# Kajtu_-DSP_analog_in.net
KiCad netlist of a schematic drawn in Altium Designer
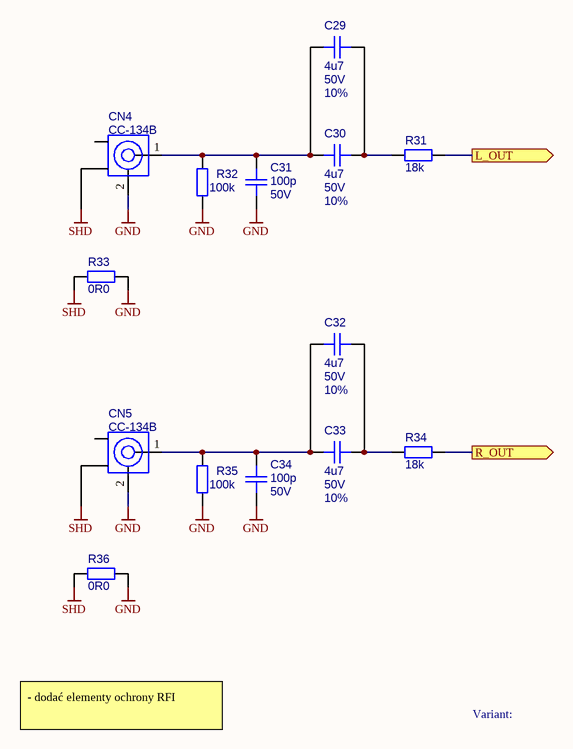
[diagram p0: Kajtuś-DSP_analog_in.SchDoc]

(export (version "E")
  (design (tool "Eeschema 10.0.6"))
  (components
    (comp (ref "C29")
      (value "4u7")
      (footprint "C_R5-L7.2-W7.2-H13")
      (description "Kondensator tworzywowy")
      (fields
        (field (name "PART NUMBER") "C_R5-L7.2-W7.2-H13_4u7_50V_MKS2_10%")
        (field (name "MANUFACTURER") "Wima")
        (field (name "VOLTAGE") "50V")
        (field (name "TOLERANCE") "10%")
      )
      (libsource (lib "AD_ostry_intlib") (part "C_R5-L7.2-W7.2-H13_4u7_50V_MKS2_10%"))
    )
    (comp (ref "C30")
      (value "4u7")
      (footprint "C_R5-L7.2-W7.2-H13")
      (description "Kondensator tworzywowy")
      (fields
        (field (name "PART NUMBER") "C_R5-L7.2-W7.2-H13_4u7_50V_MKS2_10%")
        (field (name "MANUFACTURER") "Wima")
        (field (name "VOLTAGE") "50V")
        (field (name "TOLERANCE") "10%")
      )
      (libsource (lib "AD_ostry_intlib") (part "C_R5-L7.2-W7.2-H13_4u7_50V_MKS2_10%"))
    )
    (comp (ref "C31")
      (value "100p")
      (footprint "C_0603_MA")
      (description "Kondensator ceramiczny SMD")
      (fields
        (field (name "PART NUMBER") "C_0603_100p_50V_COG")
        (field (name "MANUFACTURER") "KEMET")
        (field (name "VOLTAGE") "50V")
      )
      (libsource (lib "AD_ostry_intlib") (part "C_0603_100p_50V_COG"))
    )
    (comp (ref "C32")
      (value "4u7")
      (footprint "C_R5-L7.2-W7.2-H13")
      (description "Kondensator tworzywowy")
      (fields
        (field (name "PART NUMBER") "C_R5-L7.2-W7.2-H13_4u7_50V_MKS2_10%")
        (field (name "MANUFACTURER") "Wima")
        (field (name "VOLTAGE") "50V")
        (field (name "TOLERANCE") "10%")
      )
      (libsource (lib "AD_ostry_intlib") (part "C_R5-L7.2-W7.2-H13_4u7_50V_MKS2_10%"))
    )
    (comp (ref "C33")
      (value "4u7")
      (footprint "C_R5-L7.2-W7.2-H13")
      (description "Kondensator tworzywowy")
      (fields
        (field (name "PART NUMBER") "C_R5-L7.2-W7.2-H13_4u7_50V_MKS2_10%")
        (field (name "MANUFACTURER") "Wima")
        (field (name "VOLTAGE") "50V")
        (field (name "TOLERANCE") "10%")
      )
      (libsource (lib "AD_ostry_intlib") (part "C_R5-L7.2-W7.2-H13_4u7_50V_MKS2_10%"))
    )
    (comp (ref "C34")
      (value "100p")
      (footprint "C_0603_MA")
      (description "Kondensator ceramiczny SMD")
      (fields
        (field (name "PART NUMBER") "C_0603_100p_50V_COG")
        (field (name "MANUFACTURER") "KEMET")
        (field (name "VOLTAGE") "50V")
      )
      (libsource (lib "AD_ostry_intlib") (part "C_0603_100p_50V_COG"))
    )
    (comp (ref "CN4")
      (value "CC-134B")
      (footprint "CN_RCA_CC-134x")
      (description "Gniazdo RCA, żeńskie, ekranowane, kątowe 90°; do druku, THT, niklowane")
      (fields (field (name "PART NUMBER") "CN_RCA_CC-134B") (field (name "MANUFACTURER") "??"))
      (libsource (lib "AD_ostry_intlib") (part "CN_RCA_CC-134B"))
    )
    (comp (ref "CN5")
      (value "CC-134B")
      (footprint "CN_RCA_CC-134x")
      (description "Gniazdo RCA, żeńskie, ekranowane, kątowe 90°; do druku, THT, niklowane")
      (fields (field (name "PART NUMBER") "CN_RCA_CC-134B") (field (name "MANUFACTURER") "??"))
      (libsource (lib "AD_ostry_intlib") (part "CN_RCA_CC-134B"))
    )
    (comp (ref "R31")
      (value "18k")
      (footprint "R_1206_MA")
      (description "SMD resistor")
      (fields (field (name "PART NUMBER") "?"))
      (libsource (lib "AD_ostry_intlib") (part "R_SMD_generic"))
    )
    (comp (ref "R32")
      (value "100k")
      (footprint "R_0603_MA")
      (description "Rezystor SMD")
      (fields (field (name "MANUFACTURER") "Royal Ohm") (field (name "PART NUMBER") "R_0603_100k_5%"))
      (libsource (lib "AD_ostry_intlib") (part "R_0603_100k_5%"))
    )
    (comp (ref "R33")
      (value "0R0")
      (footprint "R_0603_MA")
      (description "Rezystor SMD")
      (fields (field (name "PART NUMBER") "R_0603_0R0_5%") (field (name "MANUFACTURER") "Royal Ohm"))
      (libsource (lib "AD_ostry_intlib") (part "R_0603_0R0_5%"))
    )
    (comp (ref "R34")
      (value "18k")
      (footprint "R_1206_MA")
      (description "SMD resistor")
      (fields (field (name "PART NUMBER") "?"))
      (libsource (lib "AD_ostry_intlib") (part "R_SMD_generic"))
    )
    (comp (ref "R35")
      (value "100k")
      (footprint "R_0603_MA")
      (description "Rezystor SMD")
      (fields (field (name "MANUFACTURER") "Royal Ohm") (field (name "PART NUMBER") "R_0603_100k_5%"))
      (libsource (lib "AD_ostry_intlib") (part "R_0603_100k_5%"))
    )
    (comp (ref "R36")
      (value "0R0")
      (footprint "R_0603_MA")
      (description "Rezystor SMD")
      (fields (field (name "PART NUMBER") "R_0603_0R0_5%") (field (name "MANUFACTURER") "Royal Ohm"))
      (libsource (lib "AD_ostry_intlib") (part "R_0603_0R0_5%"))
    )
  )
  (nets
    (net (code "1") (name "/L_OUT") (class "Default")
      (node (ref "R31") (pin "2") (pinfunction "2_2") (pintype "passive"))
    )
    (net (code "2") (name "/R_OUT") (class "Default")
      (node (ref "R34") (pin "2") (pinfunction "2_2") (pintype "passive"))
    )
    (net (code "3") (name "GND") (class "Default")
      (node (ref "C31") (pin "2") (pinfunction "2_2") (pintype "passive"))
      (node (ref "C34") (pin "2") (pinfunction "2_2") (pintype "passive"))
      (node (ref "CN4") (pin "2") (pinfunction "2_2") (pintype "passive"))
      (node (ref "CN5") (pin "2") (pinfunction "2_2") (pintype "passive"))
      (node (ref "R32") (pin "2") (pinfunction "2_2") (pintype "passive"))
      (node (ref "R33") (pin "2") (pinfunction "2_2") (pintype "passive"))
      (node (ref "R35") (pin "2") (pinfunction "2_2") (pintype "passive"))
      (node (ref "R36") (pin "2") (pinfunction "2_2") (pintype "passive"))
    )
    (net (code "4") (name "Net-(C29-Pad1)") (class "Default")
      (node (ref "C29") (pin "1") (pinfunction "1_1") (pintype "passive"))
      (node (ref "C30") (pin "1") (pinfunction "1_1") (pintype "passive"))
      (node (ref "C31") (pin "1") (pinfunction "1_1") (pintype "passive"))
      (node (ref "CN4") (pin "1") (pinfunction "1_1") (pintype "passive"))
      (node (ref "R32") (pin "1") (pinfunction "1_1") (pintype "passive"))
    )
    (net (code "5") (name "Net-(C29-Pad2)") (class "Default")
      (node (ref "C29") (pin "2") (pinfunction "2_2") (pintype "passive"))
      (node (ref "C30") (pin "2") (pinfunction "2_2") (pintype "passive"))
      (node (ref "R31") (pin "1") (pinfunction "1_1") (pintype "passive"))
    )
    (net (code "6") (name "Net-(C32-Pad1)") (class "Default")
      (node (ref "C32") (pin "1") (pinfunction "1_1") (pintype "passive"))
      (node (ref "C33") (pin "1") (pinfunction "1_1") (pintype "passive"))
      (node (ref "C34") (pin "1") (pinfunction "1_1") (pintype "passive"))
      (node (ref "CN5") (pin "1") (pinfunction "1_1") (pintype "passive"))
      (node (ref "R35") (pin "1") (pinfunction "1_1") (pintype "passive"))
    )
    (net (code "7") (name "Net-(C32-Pad2)") (class "Default")
      (node (ref "C32") (pin "2") (pinfunction "2_2") (pintype "passive"))
      (node (ref "C33") (pin "2") (pinfunction "2_2") (pintype "passive"))
      (node (ref "R34") (pin "1") (pinfunction "1_1") (pintype "passive"))
    )
    (net (code "8") (name "SHD") (class "Default")
      (node (ref "CN4") (pin "SH2") (pinfunction "SH2_SH2") (pintype "passive"))
      (node (ref "CN5") (pin "SH2") (pinfunction "SH2_SH2") (pintype "passive"))
      (node (ref "R33") (pin "1") (pinfunction "1_1") (pintype "passive"))
      (node (ref "R36") (pin "1") (pinfunction "1_1") (pintype "passive"))
    )
    (net (code "9") (name "unconnected-(CN4-PadSH1)") (class "Default")
      (node (ref "CN4") (pin "SH1") (pinfunction "SH1_SH1") (pintype "passive"))
    )
    (net (code "10") (name "unconnected-(CN5-PadSH1)") (class "Default")
      (node (ref "CN5") (pin "SH1") (pinfunction "SH1_SH1") (pintype "passive"))
    )
  )
)
